# rectifier.net
KiCad netlist of a schematic drawn in EAGLE
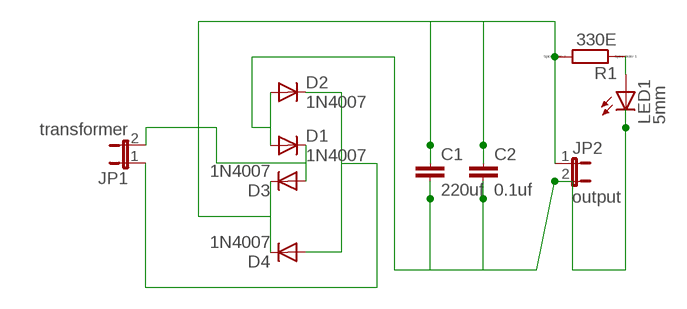
[diagram p0: schematic, sheet 1]

(export (version "E")
  (design (tool "Eeschema 10.0.6"))
  (components
    (comp (ref "C1")
      (value "220uf")
      (footprint "eagle-import:C5B7.2")
      (libsource (lib "eagle-import") (part "C5/7.2"))
    )
    (comp (ref "C2")
      (value "0.1uf")
      (footprint "eagle-import:C2.5-3")
      (libsource (lib "eagle-import") (part "C2,5-3"))
    )
    (comp (ref "D1")
      (value "1N4007")
      (footprint "eagle-import:DO41-10")
      (libsource (lib "eagle-import") (part "1N4004"))
    )
    (comp (ref "D2")
      (value "1N4007")
      (footprint "eagle-import:DO41-10")
      (libsource (lib "eagle-import") (part "1N4004"))
    )
    (comp (ref "D3")
      (value "1N4007")
      (footprint "eagle-import:DO41-10")
      (libsource (lib "eagle-import") (part "1N4004"))
    )
    (comp (ref "D4")
      (value "1N4007")
      (footprint "eagle-import:DO41-10")
      (libsource (lib "eagle-import") (part "1N4004"))
    )
    (comp (ref "JP1")
      (value "transformer")
      (footprint "eagle-import:JP1")
      (libsource (lib "eagle-import") (part "JP1E"))
    )
    (comp (ref "JP2")
      (value "output")
      (footprint "eagle-import:JP1")
      (libsource (lib "eagle-import") (part "JP1E"))
    )
    (comp (ref "LED1")
      (value "5mm")
      (footprint "eagle-import:LED5MM")
      (libsource (lib "eagle-import") (part "LED5MM"))
    )
    (comp (ref "R1")
      (value "330E")
      (footprint "eagle-import:0204_7")
      (libsource (lib "eagle-import") (part "R0204/7"))
    )
  )
  (nets
    (net (code "1") (name "Net-(C1-Pad1)") (class "Default")
      (node (ref "C1") (pin "1") (pinfunction "1_1") (pintype "passive"))
      (node (ref "C2") (pin "1") (pinfunction "1_1") (pintype "passive"))
      (node (ref "D3") (pin "C") (pinfunction "C_C") (pintype "passive"))
      (node (ref "D4") (pin "C") (pinfunction "C_C") (pintype "passive"))
      (node (ref "JP2") (pin "1") (pinfunction "1_1") (pintype "passive"))
      (node (ref "R1") (pin "2") (pinfunction "2_2") (pintype "passive"))
    )
    (net (code "2") (name "Net-(D1-PadC)") (class "Default")
      (node (ref "D1") (pin "C") (pinfunction "C_C") (pintype "passive"))
      (node (ref "D3") (pin "A") (pinfunction "A_A") (pintype "passive"))
      (node (ref "JP1") (pin "2") (pinfunction "2_2") (pintype "passive"))
    )
    (net (code "3") (name "Net-(D2-PadC)") (class "Default")
      (node (ref "D2") (pin "C") (pinfunction "C_C") (pintype "passive"))
      (node (ref "D4") (pin "A") (pinfunction "A_A") (pintype "passive"))
      (node (ref "JP1") (pin "1") (pinfunction "1_1") (pintype "passive"))
    )
    (net (code "4") (name "Net-(LED1-C)") (class "Default")
      (node (ref "C1") (pin "2") (pinfunction "2_2") (pintype "passive"))
      (node (ref "C2") (pin "2") (pinfunction "2_2") (pintype "passive"))
      (node (ref "D1") (pin "A") (pinfunction "A_A") (pintype "passive"))
      (node (ref "D2") (pin "A") (pinfunction "A_A") (pintype "passive"))
      (node (ref "JP2") (pin "2") (pinfunction "2_2") (pintype "passive"))
      (node (ref "LED1") (pin "K") (pinfunction "C_K") (pintype "passive"))
    )
    (net (code "5") (name "Net-(LED1-PadA)") (class "Default")
      (node (ref "LED1") (pin "A") (pinfunction "A_A") (pintype "passive"))
      (node (ref "R1") (pin "1") (pinfunction "1_1") (pintype "passive"))
    )
  )
)
